# LV2.net
KiCad netlist of a schematic drawn in Altium Designer
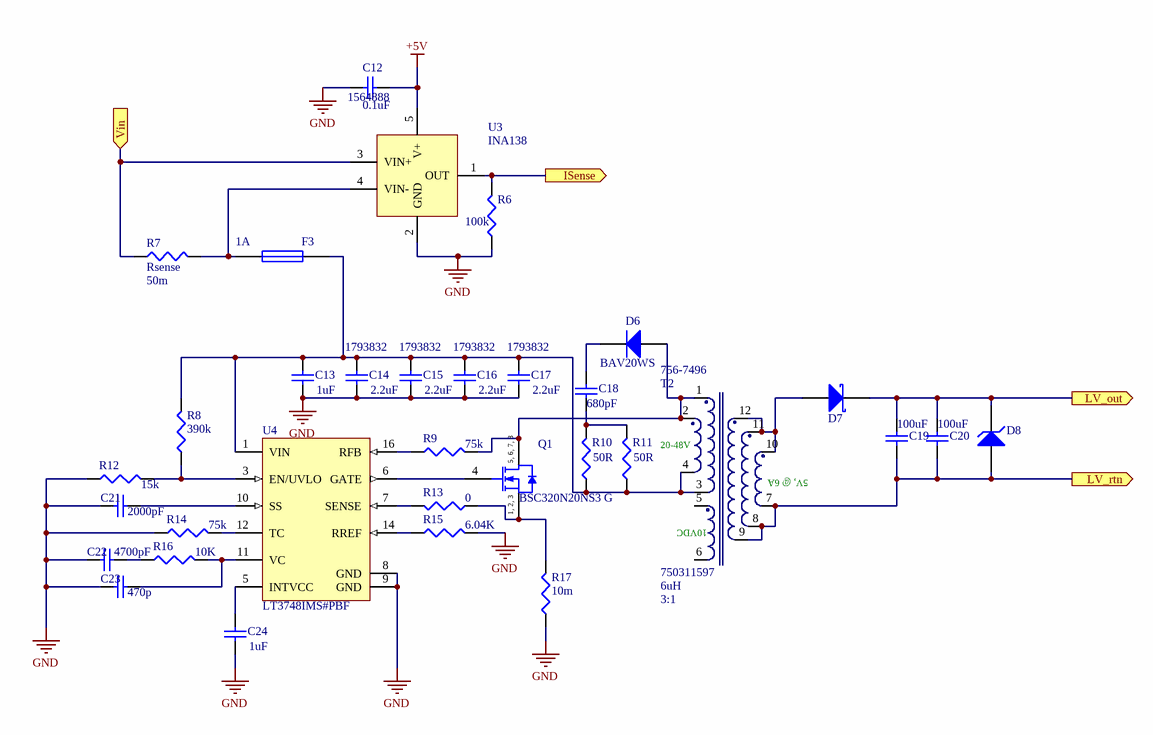
[diagram p0: LV2.schdoc]

(export (version "E")
  (design (tool "Eeschema 10.0.6"))
  (components
    (comp (ref "C12")
      (value "0.1uF")
      (footprint "1608[0603]")
      (description "Capacitor (Semiconductor SIM Model)")
      (fields
        (field (name "PARTNO") "CC0603KRX7R9BB104")
        (field (name "Comment") "Cap Semi")
        (field (name "PUBLISHER") "Altium Limited")
      )
      (libsource (lib "Miscellaneous Devices") (part "Cap Semi"))
    )
    (comp (ref "C13")
      (value "1uF")
      (footprint "C0805")
      (description "Capacitor (Semiconductor SIM Model)")
      (fields
        (field (name "PARTNO") "MC0805F105Z500CT")
        (field (name "Comment") "Cap Semi")
        (field (name "PUBLISHER") "Altium Limited")
      )
      (libsource (lib "Miscellaneous Devices") (part "Cap Semi"))
    )
    (comp (ref "C14")
      (value "2.2uF")
      (footprint "C1210")
      (description "Capacitor (Semiconductor SIM Model)")
      (fields
        (field (name "PARTNO") "C1210C225K1RACTU")
        (field (name "SUPPLIER PART NUMBER 1") "1793832")
        (field (name "Comment") "Cap Semi")
        (field (name "PUBLISHER") "Altium Limited")
      )
      (libsource (lib "Miscellaneous Devices") (part "Cap Semi"))
    )
    (comp (ref "C15")
      (value "2.2uF")
      (footprint "C1210")
      (description "Capacitor (Semiconductor SIM Model)")
      (fields
        (field (name "PARTNO") "C1210C225K1RACTU")
        (field (name "SUPPLIER PART NUMBER 1") "1793832")
        (field (name "Comment") "Cap Semi")
        (field (name "PUBLISHER") "Altium Limited")
      )
      (libsource (lib "Miscellaneous Devices") (part "Cap Semi"))
    )
    (comp (ref "C16")
      (value "2.2uF")
      (footprint "C1210")
      (description "Capacitor (Semiconductor SIM Model)")
      (fields
        (field (name "PARTNO") "C1210C225K1RACTU")
        (field (name "SUPPLIER PART NUMBER 1") "1793832")
        (field (name "Comment") "Cap Semi")
        (field (name "PUBLISHER") "Altium Limited")
      )
      (libsource (lib "Miscellaneous Devices") (part "Cap Semi"))
    )
    (comp (ref "C17")
      (value "2.2uF")
      (footprint "C1210")
      (description "Capacitor (Semiconductor SIM Model)")
      (fields
        (field (name "PARTNO") "C1210C225K1RACTU")
        (field (name "SUPPLIER PART NUMBER 1") "1793832")
        (field (name "Comment") "Cap Semi")
        (field (name "PUBLISHER") "Altium Limited")
      )
      (libsource (lib "Miscellaneous Devices") (part "Cap Semi"))
    )
    (comp (ref "C18")
      (value "680pF")
      (description "Capacitor (Semiconductor SIM Model)")
      (fields
        (field (name "PARTNO") "08055A221JAT2A")
        (field (name "Comment") "Cap Semi")
        (field (name "PUBLISHER") "Altium Limited")
      )
      (libsource (lib "Miscellaneous Devices") (part "Cap Semi"))
    )
    (comp (ref "C19")
      (value "100uF")
      (footprint "C1210")
      (description "Capacitor (Semiconductor SIM Model)")
      (fields
        (field (name "PARTNO") "C3225X5R0J107M250AC")
        (field (name "Comment") "Cap Semi")
        (field (name "PUBLISHER") "Altium Limited")
      )
      (libsource (lib "Miscellaneous Devices") (part "Cap Semi"))
    )
    (comp (ref "C20")
      (value "100uF")
      (footprint "C1210")
      (description "Capacitor (Semiconductor SIM Model)")
      (fields
        (field (name "PARTNO") "C3225X5R0J107M250AC")
        (field (name "Comment") "Cap Semi")
        (field (name "PUBLISHER") "Altium Limited")
      )
      (libsource (lib "Miscellaneous Devices") (part "Cap Semi"))
    )
    (comp (ref "C21")
      (value "2000pF")
      (footprint "1608[0603]")
      (description "Capacitor (Semiconductor SIM Model)")
      (fields (field (name "Comment") "Cap Semi") (field (name "PUBLISHER") "Altium Limited"))
      (libsource (lib "Miscellaneous Devices") (part "Cap Semi"))
    )
    (comp (ref "C22")
      (value "4700pF")
      (footprint "1608[0603]")
      (description "Capacitor (Semiconductor SIM Model)")
      (fields
        (field (name "PARTNO") "04025C472KAT2A")
        (field (name "Comment") "Cap Semi")
        (field (name "PUBLISHER") "Altium Limited")
      )
      (libsource (lib "Miscellaneous Devices") (part "Cap Semi"))
    )
    (comp (ref "C23")
      (value "470p")
      (footprint "1608[0603]")
      (description "Capacitor (Semiconductor SIM Model)")
      (fields
        (field (name "PARTNO") "C1005C0G1H471J050BA")
        (field (name "Comment") "Cap Semi")
        (field (name "PUBLISHER") "Altium Limited")
      )
      (libsource (lib "Miscellaneous Devices") (part "Cap Semi"))
    )
    (comp (ref "C24")
      (value "1uF")
      (footprint "C0805")
      (description "Capacitor (Semiconductor SIM Model)")
      (fields
        (field (name "PARTNO") "MC0805F105Z500CT")
        (field (name "Comment") "Cap Semi")
        (field (name "PUBLISHER") "Altium Limited")
      )
      (libsource (lib "Miscellaneous Devices") (part "Cap Semi"))
    )
    (comp (ref "D6")
      (value "BAV20WS")
      (footprint "SOD-323")
      (description "Power Diode")
      (fields (field (name "PUBLISHER") "Altium Limited"))
      (libsource (lib "G2_LV") (part "BAV20WS"))
    )
    (comp (ref "D7")
      (value "PDS760-13")
      (footprint "PDS1040L")
      (description "Schottky Diode")
      (fields (field (name "PARTNO") "SBR15U50SP5-13") (field (name "PUBLISHER") "Altium Limited"))
      (libsource (lib "G2_LV") (part "PDS1040L"))
    )
    (comp (ref "D8")
      (value "BZT52H-B5V6")
      (footprint "SOD123F")
      (description "Zener Diode")
      (fields (field (name "PUBLISHER") "Altium Limited"))
      (libsource (lib "G2_LV") (part "BZT52H-B5V6"))
    )
    (comp (ref "F3")
      (value "~")
      (footprint "MC33192")
      (description "Fuse")
      (fields
        (field (name "TRIPPING CURRENT") "1A")
        (field (name "PARTNO") "MC33192")
        (field (name "PUBLISHER") "Altium Limited")
      )
      (libsource (lib "G2_LV") (part "Fuse 1"))
    )
    (comp (ref "Q1")
      (value "BSC320N20NS3 G")
      (footprint "INF-PG-TDSON-8-1_V")
      (fields (field (name "MANUFACTURER") "Infineon"))
      (libsource (lib "G2_LV") (part "BSC320N20NS3 G"))
    )
    (comp (ref "R6")
      (value "100k")
      (footprint "J1-0603")
      (description "Resistor")
      (fields (field (name "Comment") "Res3") (field (name "PUBLISHER") "Altium Limited"))
      (libsource (lib "Miscellaneous Devices") (part "Res3"))
    )
    (comp (ref "R7")
      (value "Rsense")
      (footprint "R6432")
      (description "CRF2512-FV-R001ELF")
      (fields
        (field (name "ALTIUM_VALUE") "50m")
        (field (name "PARTNO") "MCS3264R050FER")
        (field (name "PUBLISHER") "Altium Limited")
      )
      (libsource (lib "G2_LV") (part "Rsense"))
    )
    (comp (ref "R8")
      (value "390k")
      (footprint "J1-0603")
      (description "Resistor")
      (fields (field (name "Comment") "Res3") (field (name "PUBLISHER") "Altium Limited"))
      (libsource (lib "Miscellaneous Devices") (part "Res3"))
    )
    (comp (ref "R9")
      (value "75k")
      (footprint "J1-0603")
      (description "Resistor")
      (fields (field (name "Comment") "Res3") (field (name "PUBLISHER") "Altium Limited"))
      (libsource (lib "Miscellaneous Devices") (part "Res3"))
    )
    (comp (ref "R10")
      (value "50R")
      (description "Resistor")
      (fields (field (name "Comment") "Res3") (field (name "PUBLISHER") "Altium Limited"))
      (libsource (lib "Miscellaneous Devices") (part "Res3"))
    )
    (comp (ref "R11")
      (value "50R")
      (description "Resistor")
      (fields (field (name "Comment") "Res3") (field (name "PUBLISHER") "Altium Limited"))
      (libsource (lib "Miscellaneous Devices") (part "Res3"))
    )
    (comp (ref "R12")
      (value "15k")
      (footprint "J1-0603")
      (description "Resistor")
      (fields (field (name "Comment") "Res3") (field (name "PUBLISHER") "Altium Limited"))
      (libsource (lib "Miscellaneous Devices") (part "Res3"))
    )
    (comp (ref "R13")
      (value "0")
      (footprint "J1-0603")
      (description "Resistor")
      (fields (field (name "Comment") "Res3") (field (name "PUBLISHER") "Altium Limited"))
      (libsource (lib "Miscellaneous Devices") (part "Res3"))
    )
    (comp (ref "R14")
      (value "75k")
      (footprint "J1-0603")
      (description "Resistor")
      (fields (field (name "Comment") "Res3") (field (name "PUBLISHER") "Altium Limited"))
      (libsource (lib "Miscellaneous Devices") (part "Res3"))
    )
    (comp (ref "R15")
      (value "6.04K")
      (footprint "J1-0603")
      (description "Resistor")
      (fields (field (name "Comment") "Res3") (field (name "PUBLISHER") "Altium Limited"))
      (libsource (lib "Miscellaneous Devices") (part "Res3"))
    )
    (comp (ref "R16")
      (value "10K")
      (footprint "J1-0603")
      (description "Resistor")
      (fields (field (name "Comment") "Res3") (field (name "PUBLISHER") "Altium Limited"))
      (libsource (lib "Miscellaneous Devices") (part "Res3"))
    )
    (comp (ref "R17")
      (value "10m")
      (footprint "C1206")
      (description "Resistor")
      (fields
        (field (name "PARTNO") "LRMAM1206-R01FT5")
        (field (name "Comment") "Res3")
        (field (name "PUBLISHER") "Altium Limited")
      )
      (libsource (lib "Miscellaneous Devices") (part "Res3"))
    )
    (comp (ref "T2")
      (value "750311597")
      (footprint "EFD20")
      (description "Flyback Transformer suitable or LT3573/ LT3574/ LT3575/ LT3748 WE-FB, Ui=20-48V")
      (fields
        (field (name "SUPPLIER PART NUMBER 1") "756-7496")
        (field (name "LPRI") "6uH")
        (field (name "N") "3:1")
      )
      (libsource (lib "WE-FB Flyback Transformer suitable for LT3573_LT3574_LT3575_LT3748") (part "750311597"))
    )
    (comp (ref "U3")
      (value "INA138")
      (footprint "SOT-23")
      (fields (field (name "PARTNO") "INA138NA/250") (field (name "SUPPLIER PART NUMBER 1") "1564888"))
      (libsource (lib "PCB_Project") (part "INA138"))
    )
    (comp (ref "U4")
      (value "LT3748IMS#PBF")
      (footprint "LT-MS-16-4PR_N")
      (description "Isolated Flyback Controller, 16-pin SOP (MS-16), -40 to 125 degC, Pb-Free")
      (fields (field (name "MANUFACTURER") "Linear Technology"))
      (libsource (lib "Linear Technology Power Management Switching Regulator LT1074-LT8705") (part "LT3748IMS#PBF"))
    )
  )
  (nets
    (net (code "1") (name "+5V") (class "Default")
      (node (ref "C12") (pin "2") (pinfunction "2_2") (pintype "passive"))
      (node (ref "U3") (pin "5") (pinfunction "V+_5") (pintype "passive"))
    )
    (net (code "2") (name "/ISense") (class "Default")
      (node (ref "R6") (pin "2") (pinfunction "2_2") (pintype "passive"))
      (node (ref "U3") (pin "1") (pinfunction "OUT_1") (pintype "passive"))
    )
    (net (code "3") (name "/LV_out") (class "Default")
      (node (ref "C19") (pin "2") (pinfunction "2_2") (pintype "passive"))
      (node (ref "C20") (pin "2") (pinfunction "2_2") (pintype "passive"))
      (node (ref "D7") (pin "2") (pinfunction "K_2") (pintype "passive"))
      (node (ref "D8") (pin "2") (pinfunction "K_2") (pintype "passive"))
    )
    (net (code "4") (name "/LV_rtn") (class "Default")
      (node (ref "C19") (pin "1") (pinfunction "1_1") (pintype "passive"))
      (node (ref "C20") (pin "1") (pinfunction "1_1") (pintype "passive"))
      (node (ref "D8") (pin "1") (pinfunction "A_1") (pintype "passive"))
      (node (ref "T2") (pin "7") (pinfunction "7_7") (pintype "passive"))
      (node (ref "T2") (pin "8") (pinfunction "8_8") (pintype "passive"))
      (node (ref "T2") (pin "9") (pinfunction "9_9") (pintype "passive"))
    )
    (net (code "5") (name "/Vin") (class "Default")
      (node (ref "R7") (pin "1") (pinfunction "1_1") (pintype "passive"))
      (node (ref "U3") (pin "3") (pinfunction "VIN+_3") (pintype "passive"))
    )
    (net (code "6") (name "GND") (class "Default")
      (node (ref "C12") (pin "1") (pinfunction "1_1") (pintype "passive"))
      (node (ref "C13") (pin "1") (pinfunction "1_1") (pintype "passive"))
      (node (ref "C14") (pin "1") (pinfunction "1_1") (pintype "passive"))
      (node (ref "C15") (pin "1") (pinfunction "1_1") (pintype "passive"))
      (node (ref "C16") (pin "1") (pinfunction "1_1") (pintype "passive"))
      (node (ref "C17") (pin "1") (pinfunction "1_1") (pintype "passive"))
      (node (ref "C21") (pin "1") (pinfunction "1_1") (pintype "passive"))
      (node (ref "C22") (pin "1") (pinfunction "1_1") (pintype "passive"))
      (node (ref "C23") (pin "1") (pinfunction "1_1") (pintype "passive"))
      (node (ref "C24") (pin "1") (pinfunction "1_1") (pintype "passive"))
      (node (ref "R12") (pin "1") (pinfunction "1_1") (pintype "passive"))
      (node (ref "R14") (pin "1") (pinfunction "1_1") (pintype "passive"))
      (node (ref "R15") (pin "2") (pinfunction "2_2") (pintype "passive"))
      (node (ref "R17") (pin "1") (pinfunction "1_1") (pintype "passive"))
      (node (ref "R6") (pin "1") (pinfunction "1_1") (pintype "passive"))
      (node (ref "U3") (pin "2") (pinfunction "GND_2") (pintype "passive"))
      (node (ref "U4") (pin "8") (pinfunction "GND_8") (pintype "power_in"))
      (node (ref "U4") (pin "9") (pinfunction "GND_9") (pintype "power_in"))
    )
    (net (code "7") (name "Net-(C18-Pad2)") (class "Default")
      (node (ref "C18") (pin "2") (pinfunction "2_2") (pintype "passive"))
      (node (ref "R10") (pin "2") (pinfunction "2_2") (pintype "passive"))
      (node (ref "R11") (pin "2") (pinfunction "2_2") (pintype "passive"))
    )
    (net (code "8") (name "Net-(C22-Pad2)") (class "Default")
      (node (ref "C22") (pin "2") (pinfunction "2_2") (pintype "passive"))
      (node (ref "R16") (pin "1") (pinfunction "1_1") (pintype "passive"))
    )
    (net (code "9") (name "Net-(D6-A)") (class "Default")
      (node (ref "D6") (pin "2") (pinfunction "A_2") (pintype "passive"))
      (node (ref "Q1") (pin "5") (pinfunction "DRAIN_5") (pintype "passive"))
      (node (ref "Q1") (pin "6") (pinfunction "DRAIN_6") (pintype "passive"))
      (node (ref "Q1") (pin "7") (pinfunction "DRAIN_7") (pintype "passive"))
      (node (ref "Q1") (pin "8") (pinfunction "DRAIN_8") (pintype "passive"))
      (node (ref "R9") (pin "2") (pinfunction "2_2") (pintype "passive"))
      (node (ref "T2") (pin "1") (pinfunction "1_1") (pintype "passive"))
      (node (ref "T2") (pin "2") (pinfunction "2_2") (pintype "passive"))
    )
    (net (code "10") (name "Net-(D6-K)") (class "Default")
      (node (ref "C18") (pin "1") (pinfunction "1_1") (pintype "passive"))
      (node (ref "D6") (pin "1") (pinfunction "K_1") (pintype "passive"))
    )
    (net (code "11") (name "Net-(D7-A)") (class "Default")
      (node (ref "D7") (pin "1") (pinfunction "A_1") (pintype "passive"))
      (node (ref "T2") (pin "10") (pinfunction "10_10") (pintype "passive"))
      (node (ref "T2") (pin "11") (pinfunction "11_11") (pintype "passive"))
      (node (ref "T2") (pin "12") (pinfunction "12_12") (pintype "passive"))
    )
    (net (code "12") (name "Net-(Q1-GATE)") (class "Default")
      (node (ref "Q1") (pin "4") (pinfunction "GATE_4") (pintype "passive"))
      (node (ref "U4") (pin "6") (pinfunction "GATE_6") (pintype "output"))
    )
    (net (code "13") (name "Net-(Q1-SOURCE-Pad1)") (class "Default")
      (node (ref "Q1") (pin "1") (pinfunction "SOURCE_1") (pintype "passive"))
      (node (ref "Q1") (pin "2") (pinfunction "SOURCE_2") (pintype "passive"))
      (node (ref "Q1") (pin "3") (pinfunction "SOURCE_3") (pintype "passive"))
      (node (ref "R13") (pin "1") (pinfunction "1_1") (pintype "passive"))
      (node (ref "R17") (pin "2") (pinfunction "2_2") (pintype "passive"))
    )
    (net (code "14") (name "Net-(U3-VIN-)") (class "Default")
      (node (ref "F3") (pin "1") (pinfunction "1_1") (pintype "passive"))
      (node (ref "R7") (pin "2") (pinfunction "2_2") (pintype "passive"))
      (node (ref "U3") (pin "4") (pinfunction "VIN-_4") (pintype "passive"))
    )
    (net (code "15") (name "Net-(U4-EN{slash}UVLO)") (class "Default")
      (node (ref "R12") (pin "2") (pinfunction "2_2") (pintype "passive"))
      (node (ref "R8") (pin "1") (pinfunction "1_1") (pintype "passive"))
      (node (ref "U4") (pin "3") (pinfunction "EN/UVLO_3") (pintype "input"))
    )
    (net (code "16") (name "Net-(U4-INTVCC)") (class "Default")
      (node (ref "C24") (pin "2") (pinfunction "2_2") (pintype "passive"))
      (node (ref "U4") (pin "5") (pinfunction "INTVCC_5") (pintype "power_in"))
    )
    (net (code "17") (name "Net-(U4-RFB)") (class "Default")
      (node (ref "R9") (pin "1") (pinfunction "1_1") (pintype "passive"))
      (node (ref "U4") (pin "16") (pinfunction "RFB_16") (pintype "input"))
    )
    (net (code "18") (name "Net-(U4-RREF)") (class "Default")
      (node (ref "R15") (pin "1") (pinfunction "1_1") (pintype "passive"))
      (node (ref "U4") (pin "14") (pinfunction "RREF_14") (pintype "input"))
    )
    (net (code "19") (name "Net-(U4-SENSE)") (class "Default")
      (node (ref "R13") (pin "2") (pinfunction "2_2") (pintype "passive"))
      (node (ref "U4") (pin "7") (pinfunction "SENSE_7") (pintype "input"))
    )
    (net (code "20") (name "Net-(U4-SS)") (class "Default")
      (node (ref "C21") (pin "2") (pinfunction "2_2") (pintype "passive"))
      (node (ref "U4") (pin "10") (pinfunction "SS_10") (pintype "input"))
    )
    (net (code "21") (name "Net-(U4-TC)") (class "Default")
      (node (ref "R14") (pin "2") (pinfunction "2_2") (pintype "passive"))
      (node (ref "U4") (pin "12") (pinfunction "TC_12") (pintype "passive"))
    )
    (net (code "22") (name "Net-(U4-VC)") (class "Default")
      (node (ref "C23") (pin "2") (pinfunction "2_2") (pintype "passive"))
      (node (ref "R16") (pin "2") (pinfunction "2_2") (pintype "passive"))
      (node (ref "U4") (pin "11") (pinfunction "VC_11") (pintype "passive"))
    )
    (net (code "23") (name "Net-(U4-VIN)") (class "Default")
      (node (ref "C13") (pin "2") (pinfunction "2_2") (pintype "passive"))
      (node (ref "C14") (pin "2") (pinfunction "2_2") (pintype "passive"))
      (node (ref "C15") (pin "2") (pinfunction "2_2") (pintype "passive"))
      (node (ref "C16") (pin "2") (pinfunction "2_2") (pintype "passive"))
      (node (ref "C17") (pin "2") (pinfunction "2_2") (pintype "passive"))
      (node (ref "F3") (pin "2") (pinfunction "2_2") (pintype "passive"))
      (node (ref "R10") (pin "1") (pinfunction "1_1") (pintype "passive"))
      (node (ref "R11") (pin "1") (pinfunction "1_1") (pintype "passive"))
      (node (ref "R8") (pin "2") (pinfunction "2_2") (pintype "passive"))
      (node (ref "T2") (pin "3") (pinfunction "3_3") (pintype "passive"))
      (node (ref "T2") (pin "4") (pinfunction "4_4") (pintype "passive"))
      (node (ref "U4") (pin "1") (pinfunction "VIN_1") (pintype "power_in"))
    )
    (net (code "24") (name "unconnected-(T2-Pad5)") (class "Default")
      (node (ref "T2") (pin "5") (pinfunction "5_5") (pintype "passive"))
    )
    (net (code "25") (name "unconnected-(T2-Pad6)") (class "Default")
      (node (ref "T2") (pin "6") (pinfunction "6_6") (pintype "passive"))
    )
  )
)
